# SIM7080G.net
KiCad netlist of a schematic drawn in Altium Designer
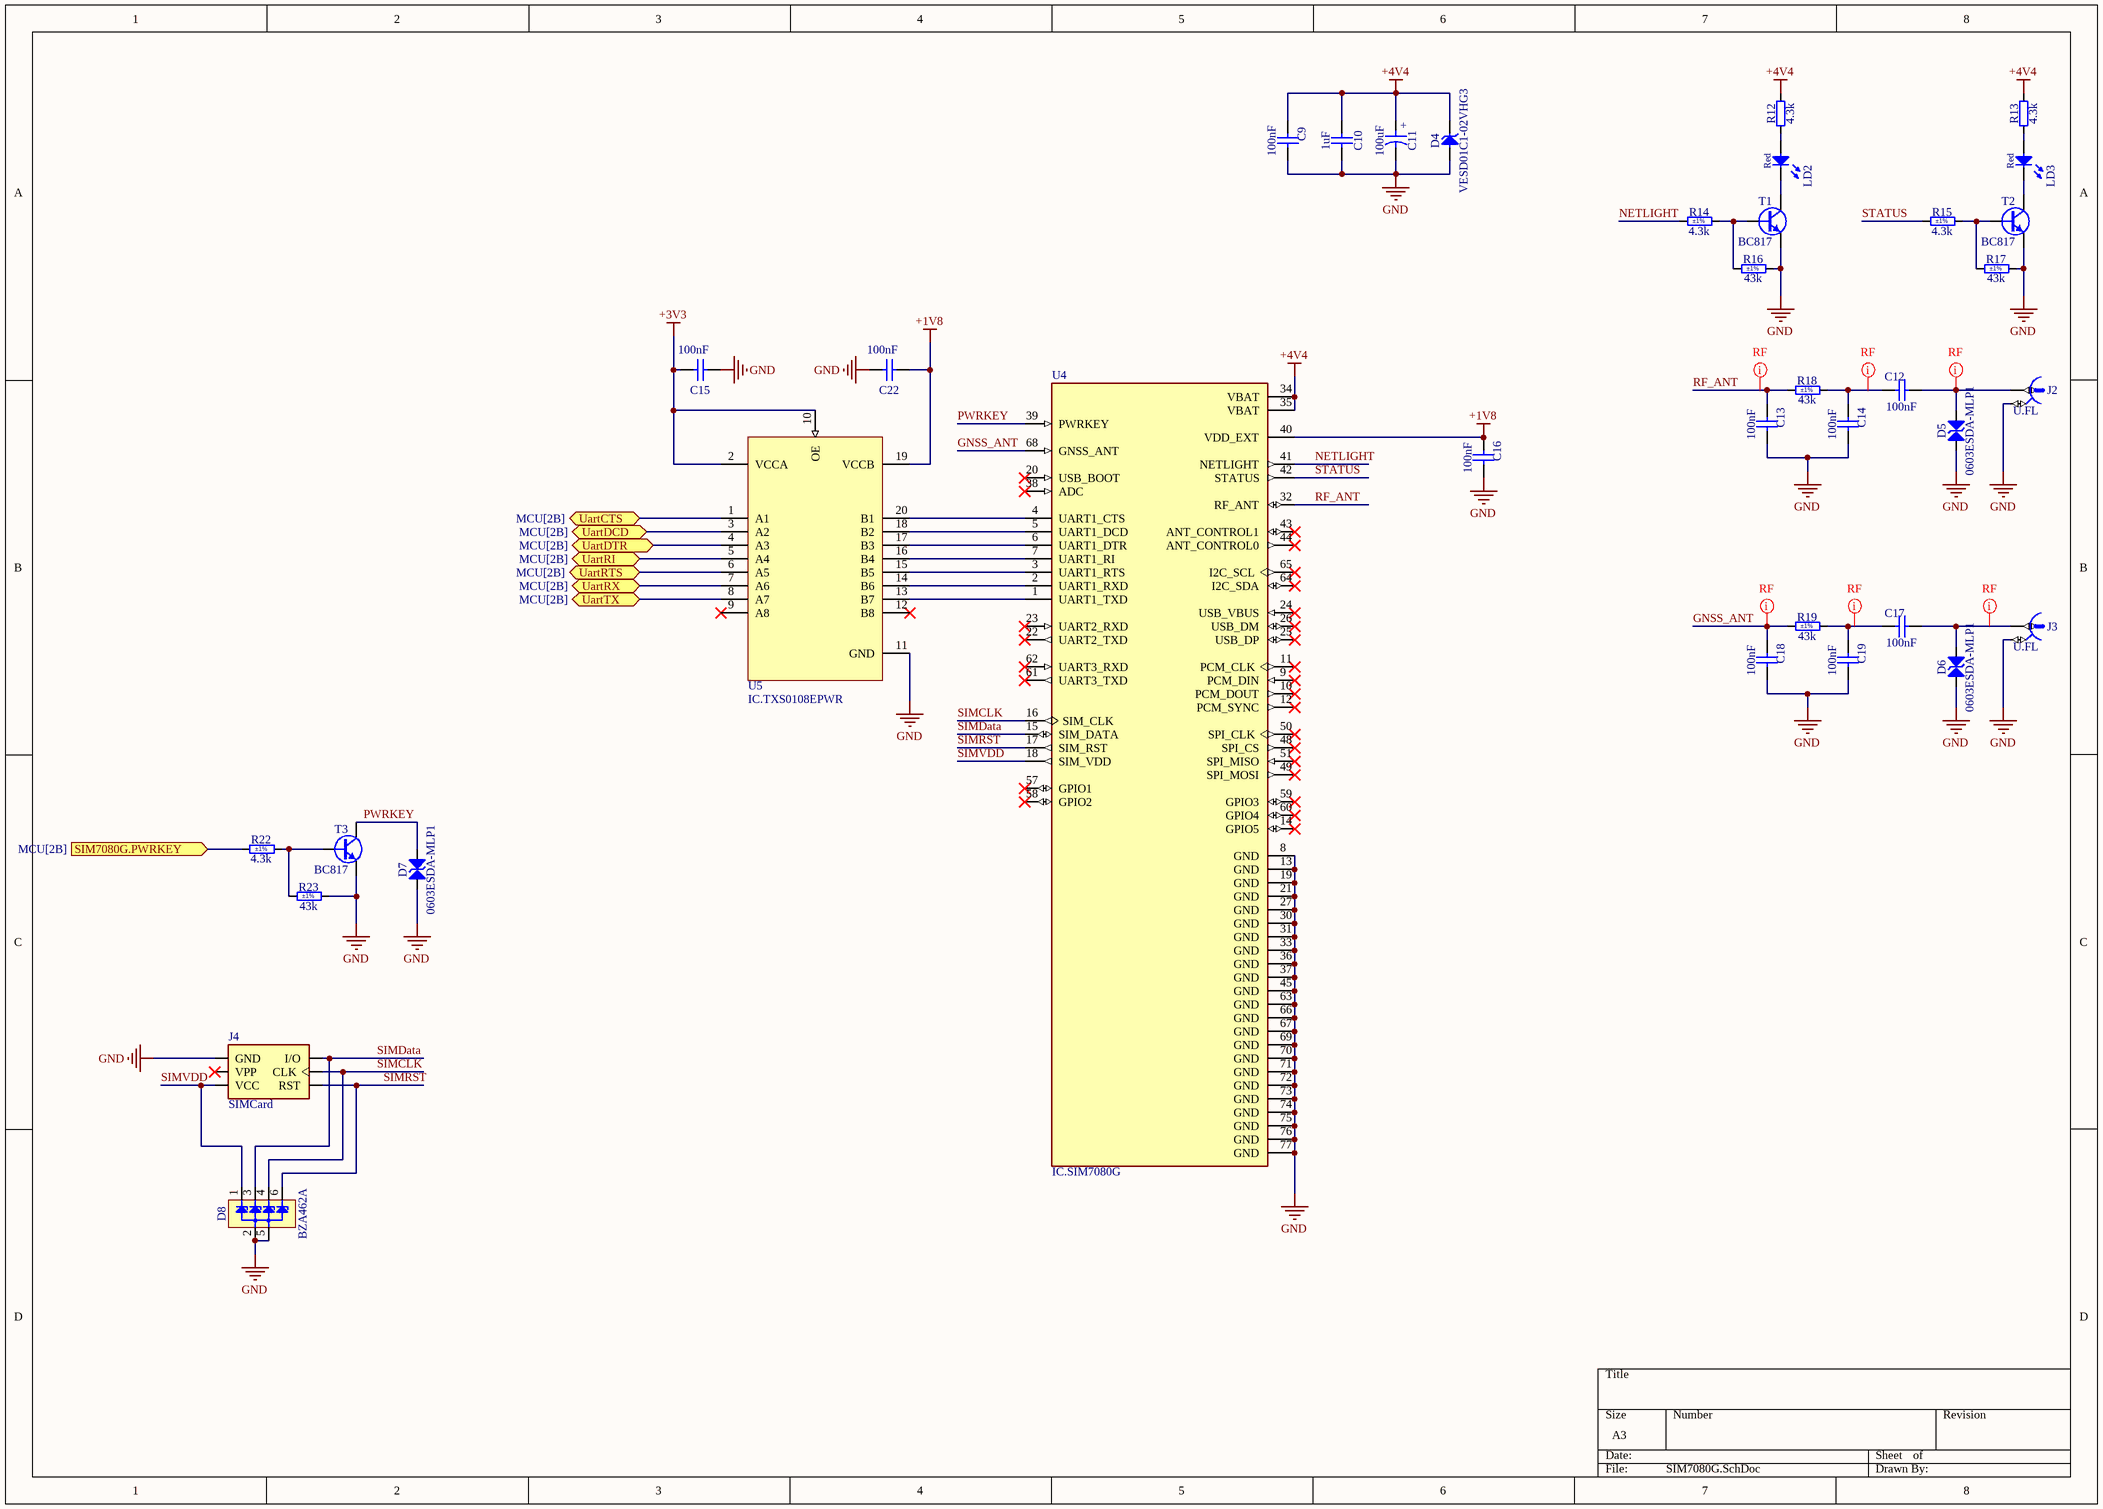
[diagram p0: SIM7080G.SchDoc]

(export (version "E")
  (design (tool "Eeschema 10.0.6"))
  (components
    (comp (ref "C9")
      (value "100nF")
      (footprint "CAPC1608X90N")
      (description "Non-polarised capacitor")
      (fields
        (field (name "PART NUMBER") "CC0603_100NF_25V_20%_X5R_TDK_CGA3E2X5R1E104M080")
        (field (name "VOLTAGE") "25V")
        (field (name "AUTHOR") "CERN DEM BC")
      )
      (libsource (lib "Capacitors") (part "Capacitor - non polarized"))
    )
    (comp (ref "C10")
      (value "1uF")
      (footprint "CAPC1608X90N")
      (description "Non-polarised capacitor")
      (fields
        (field (name "PART NUMBER") "CC0603_1UF_10V_10%_X5R")
        (field (name "VOLTAGE") "10V")
        (field (name "AUTHOR") "CERN DEM HF")
      )
      (libsource (lib "Capacitors") (part "Capacitor - non polarized"))
    )
    (comp (ref "C11")
      (value "100uF")
      (footprint "CAPAE660X540N")
      (description "Polarised capacitor")
      (fields
        (field (name "PART NUMBER") "CAE660-540_100UF_6.3V_20%")
        (field (name "VOLTAGE") "6.3V")
        (field (name "AUTHOR") "CERN DEM JLC")
      )
      (libsource (lib "Capacitors") (part "Capacitor - polarized"))
    )
    (comp (ref "C12")
      (value "100nF")
      (footprint "CAPC1608X90N")
      (description "Non-polarised capacitor")
      (fields
        (field (name "PART NUMBER") "CC0603_100NF_25V_20%_X5R_TDK_CGA3E2X5R1E104M080")
        (field (name "VOLTAGE") "25V")
        (field (name "AUTHOR") "CERN DEM BC")
      )
      (libsource (lib "Capacitors") (part "Capacitor - non polarized"))
    )
    (comp (ref "C13")
      (value "100nF")
      (footprint "CAPC1608X90N")
      (description "Non-polarised capacitor")
      (fields
        (field (name "PART NUMBER") "CC0603_100NF_25V_20%_X5R_TDK_CGA3E2X5R1E104M080")
        (field (name "VOLTAGE") "25V")
        (field (name "AUTHOR") "CERN DEM BC")
      )
      (libsource (lib "Capacitors") (part "Capacitor - non polarized"))
    )
    (comp (ref "C14")
      (value "100nF")
      (footprint "CAPC1608X90N")
      (description "Non-polarised capacitor")
      (fields
        (field (name "PART NUMBER") "CC0603_100NF_25V_20%_X5R_TDK_CGA3E2X5R1E104M080")
        (field (name "VOLTAGE") "25V")
        (field (name "AUTHOR") "CERN DEM BC")
      )
      (libsource (lib "Capacitors") (part "Capacitor - non polarized"))
    )
    (comp (ref "C15")
      (value "100nF")
      (footprint "CAPC1608X90N")
      (description "Non-polarised capacitor")
      (fields
        (field (name "PART NUMBER") "CC0603_100NF_25V_20%_X5R_TDK_CGA3E2X5R1E104M080")
        (field (name "VOLTAGE") "25V")
        (field (name "AUTHOR") "CERN DEM BC")
      )
      (libsource (lib "Capacitors") (part "Capacitor - non polarized"))
    )
    (comp (ref "C16")
      (value "100nF")
      (footprint "CAPC1608X90N")
      (description "Non-polarised capacitor")
      (fields
        (field (name "PART NUMBER") "CC0603_100NF_25V_20%_X5R_TDK_CGA3E2X5R1E104M080")
        (field (name "VOLTAGE") "25V")
        (field (name "AUTHOR") "CERN DEM BC")
      )
      (libsource (lib "Capacitors") (part "Capacitor - non polarized"))
    )
    (comp (ref "C17")
      (value "100nF")
      (footprint "CAPC1608X90N")
      (description "Non-polarised capacitor")
      (fields
        (field (name "PART NUMBER") "CC0603_100NF_25V_20%_X5R_TDK_CGA3E2X5R1E104M080")
        (field (name "VOLTAGE") "25V")
        (field (name "AUTHOR") "CERN DEM BC")
      )
      (libsource (lib "Capacitors") (part "Capacitor - non polarized"))
    )
    (comp (ref "C18")
      (value "100nF")
      (footprint "CAPC1608X90N")
      (description "Non-polarised capacitor")
      (fields
        (field (name "PART NUMBER") "CC0603_100NF_25V_20%_X5R_TDK_CGA3E2X5R1E104M080")
        (field (name "VOLTAGE") "25V")
        (field (name "AUTHOR") "CERN DEM BC")
      )
      (libsource (lib "Capacitors") (part "Capacitor - non polarized"))
    )
    (comp (ref "C19")
      (value "100nF")
      (footprint "CAPC1608X90N")
      (description "Non-polarised capacitor")
      (fields
        (field (name "PART NUMBER") "CC0603_100NF_25V_20%_X5R_TDK_CGA3E2X5R1E104M080")
        (field (name "VOLTAGE") "25V")
        (field (name "AUTHOR") "CERN DEM BC")
      )
      (libsource (lib "Capacitors") (part "Capacitor - non polarized"))
    )
    (comp (ref "C22")
      (value "100nF")
      (footprint "CAPC1608X90N")
      (description "Non-polarised capacitor")
      (fields
        (field (name "PART NUMBER") "CC0603_100NF_25V_20%_X5R_TDK_CGA3E2X5R1E104M080")
        (field (name "VOLTAGE") "25V")
        (field (name "AUTHOR") "CERN DEM BC")
      )
      (libsource (lib "Capacitors") (part "Capacitor - non polarized"))
    )
    (comp (ref "D4")
      (value "VESD01C1-02VHG3")
      (footprint "SODFL1608X70N")
      (description "Transient Voltage Suppressor Diode (Uni-Directional)")
      (fields
        (field (name "VOLTAGE") "1V")
        (field (name "POWER") "100W")
        (field (name "AUTHOR") "CERN DEM BC")
      )
      (libsource (lib "ICs And Semiconductors") (part "Diode TVS Uni-Directional"))
    )
    (comp (ref "D5")
      (value "0603ESDA-MLP1")
      (footprint "EATON_0603ESDA-MLP")
      (description "Transient Voltage Suppressor Diode (Bi-Directional)")
      (fields
        (field (name "VOLTAGE") "8kV")
        (field (name "MANUFACTURER") "EATON")
        (field (name "AUTHOR") "CERN DEM HF")
      )
      (libsource (lib "ICs And Semiconductors") (part "Diode TVS Bi-Directional"))
    )
    (comp (ref "D6")
      (value "0603ESDA-MLP1")
      (footprint "EATON_0603ESDA-MLP")
      (description "Transient Voltage Suppressor Diode (Bi-Directional)")
      (fields
        (field (name "VOLTAGE") "8kV")
        (field (name "MANUFACTURER") "EATON")
        (field (name "AUTHOR") "CERN DEM HF")
      )
      (libsource (lib "ICs And Semiconductors") (part "Diode TVS Bi-Directional"))
    )
    (comp (ref "D7")
      (value "0603ESDA-MLP1")
      (footprint "EATON_0603ESDA-MLP")
      (description "Transient Voltage Suppressor Diode (Bi-Directional)")
      (fields
        (field (name "VOLTAGE") "8kV")
        (field (name "MANUFACTURER") "EATON")
        (field (name "AUTHOR") "CERN DEM HF")
      )
      (libsource (lib "ICs And Semiconductors") (part "Diode TVS Bi-Directional"))
    )
    (comp (ref "D8")
      (value "BZA462A")
      (footprint "SOT95P275X110-6N")
      (description "Quadruple ESD Transient Voltage Suppressor")
      (fields
        (field (name "VOLTAGE") "15kV")
        (field (name "POWER") "24W")
        (field (name "AUTHOR") "CERN DEM JLC")
      )
      (libsource (lib "ICs And Semiconductors") (part "BZA462A"))
    )
    (comp (ref "J2")
      (value "U.FL")
      (footprint "HIROSE_U.FL-R-SMT-1(10)")
      (fields
        (field (name "PART NUMBER") "HIROSE_U.FL-R-SMT-1(10)")
        (field (name "MANUFACTURER") "HIROSE (HRS)")
        (field (name "MANUFACTURER PART NUMBER") "U.FL-R-SMT-1(10)")
        (field (name "AUTHOR") "CERN DEM JLC")
      )
      (libsource (lib "Connectors") (part "Coax_1Male_1Shield"))
    )
    (comp (ref "J3")
      (value "U.FL")
      (footprint "HIROSE_U.FL-R-SMT-1(10)")
      (fields
        (field (name "PART NUMBER") "HIROSE_U.FL-R-SMT-1(10)")
        (field (name "MANUFACTURER") "HIROSE (HRS)")
        (field (name "MANUFACTURER PART NUMBER") "U.FL-R-SMT-1(10)")
        (field (name "AUTHOR") "CERN DEM JLC")
      )
      (libsource (lib "Connectors") (part "Coax_1Male_1Shield"))
    )
    (comp (ref "J4")
      (value "SIMCard")
      (footprint "Connector.SIM805")
      (description "SIM Nano Push Pull 6P1.35mmH with Logo 3µ\" Gold No Peg")
      (fields
        (field (name "MP") "SIM8051-6-0-14-00-X-REVD")
        (field (name "MANUFACTURER") "Global Connector Technology")
      )
      (libsource (lib "ParsaAltiumSCHLIB") (part "Connector.SIM8051"))
    )
    (comp (ref "LD2")
      (value "Red")
      (footprint "LED_DIALIGHT_598-8010-107F")
      (description "LED Red 1C 2A")
      (fields
        (field (name "PART NUMBER") "LED_DIALIGHT_598-8010-107F")
        (field (name "MANUFACTURER") "DIALIGHT")
        (field (name "AUTHOR") "CERN DEM MR")
      )
      (libsource (lib "ICs And Semiconductors") (part "LED Red 1C 2A"))
    )
    (comp (ref "LD3")
      (value "Red")
      (footprint "LED_DIALIGHT_598-8010-107F")
      (description "LED Red 1C 2A")
      (fields
        (field (name "PART NUMBER") "LED_DIALIGHT_598-8010-107F")
        (field (name "MANUFACTURER") "DIALIGHT")
        (field (name "AUTHOR") "CERN DEM MR")
      )
      (libsource (lib "ICs And Semiconductors") (part "LED Red 1C 2A"))
    )
    (comp (ref "R12")
      (value "4.3k")
      (footprint "RESC1608X55N")
      (description "Resistor - 1%")
      (fields
        (field (name "PART NUMBER") "R0603_43K_1%_0.1W_100PPM")
        (field (name "POWER") "0.1W")
        (field (name "AUTHOR") "CERN DEM JLC")
      )
      (libsource (lib "Resistors") (part "Resistor - 1%"))
    )
    (comp (ref "R13")
      (value "4.3k")
      (footprint "RESC1608X55N")
      (description "Resistor - 1%")
      (fields
        (field (name "PART NUMBER") "R0603_43K_1%_0.1W_100PPM")
        (field (name "POWER") "0.1W")
        (field (name "AUTHOR") "CERN DEM JLC")
      )
      (libsource (lib "Resistors") (part "Resistor - 1%"))
    )
    (comp (ref "R14")
      (value "4.3k")
      (footprint "RESC1608X55N")
      (description "Resistor - 1%")
      (fields
        (field (name "TOLERANCE") "±1%")
        (field (name "PART NUMBER") "R0603_43K_1%_0.1W_100PPM")
        (field (name "POWER") "0.1W")
        (field (name "AUTHOR") "CERN DEM JLC")
      )
      (libsource (lib "Resistors") (part "Resistor - 1%"))
    )
    (comp (ref "R15")
      (value "4.3k")
      (footprint "RESC1608X55N")
      (description "Resistor - 1%")
      (fields
        (field (name "TOLERANCE") "±1%")
        (field (name "PART NUMBER") "R0603_43K_1%_0.1W_100PPM")
        (field (name "POWER") "0.1W")
        (field (name "AUTHOR") "CERN DEM JLC")
      )
      (libsource (lib "Resistors") (part "Resistor - 1%"))
    )
    (comp (ref "R16")
      (value "43k")
      (footprint "RESC1608X55N")
      (description "Resistor - 1%")
      (fields
        (field (name "TOLERANCE") "±1%")
        (field (name "PART NUMBER") "R0603_43K_1%_0.1W_100PPM")
        (field (name "POWER") "0.1W")
        (field (name "AUTHOR") "CERN DEM JLC")
      )
      (libsource (lib "Resistors") (part "Resistor - 1%"))
    )
    (comp (ref "R17")
      (value "43k")
      (footprint "RESC1608X55N")
      (description "Resistor - 1%")
      (fields
        (field (name "TOLERANCE") "±1%")
        (field (name "PART NUMBER") "R0603_43K_1%_0.1W_100PPM")
        (field (name "POWER") "0.1W")
        (field (name "AUTHOR") "CERN DEM JLC")
      )
      (libsource (lib "Resistors") (part "Resistor - 1%"))
    )
    (comp (ref "R18")
      (value "43k")
      (footprint "RESC1608X55N")
      (description "Resistor - 1%")
      (fields
        (field (name "TOLERANCE") "±1%")
        (field (name "PART NUMBER") "R0603_43K_1%_0.1W_100PPM")
        (field (name "POWER") "0.1W")
        (field (name "AUTHOR") "CERN DEM JLC")
      )
      (libsource (lib "Resistors") (part "Resistor - 1%"))
    )
    (comp (ref "R19")
      (value "43k")
      (footprint "RESC1608X55N")
      (description "Resistor - 1%")
      (fields
        (field (name "TOLERANCE") "±1%")
        (field (name "PART NUMBER") "R0603_43K_1%_0.1W_100PPM")
        (field (name "POWER") "0.1W")
        (field (name "AUTHOR") "CERN DEM JLC")
      )
      (libsource (lib "Resistors") (part "Resistor - 1%"))
    )
    (comp (ref "R22")
      (value "4.3k")
      (footprint "RESC1608X55N")
      (description "Resistor - 1%")
      (fields
        (field (name "TOLERANCE") "±1%")
        (field (name "PART NUMBER") "R0603_43K_1%_0.1W_100PPM")
        (field (name "POWER") "0.1W")
        (field (name "AUTHOR") "CERN DEM JLC")
      )
      (libsource (lib "Resistors") (part "Resistor - 1%"))
    )
    (comp (ref "R23")
      (value "43k")
      (footprint "RESC1608X55N")
      (description "Resistor - 1%")
      (fields
        (field (name "TOLERANCE") "±1%")
        (field (name "PART NUMBER") "R0603_43K_1%_0.1W_100PPM")
        (field (name "POWER") "0.1W")
        (field (name "AUTHOR") "CERN DEM JLC")
      )
      (libsource (lib "Resistors") (part "Resistor - 1%"))
    )
    (comp (ref "T1")
      (value "BC817")
      (footprint "SOT95P230X110-3N")
      (description "NPN Transistor")
      (fields (field (name "MANUFACTURER") "NXP SEMICONDUCTORS") (field (name "AUTHOR") "CERN DEM JLC"))
      (libsource (lib "ICs And Semiconductors") (part "NPN B1 E2 C3"))
    )
    (comp (ref "T2")
      (value "BC817")
      (footprint "SOT95P230X110-3N")
      (description "NPN Transistor")
      (fields (field (name "MANUFACTURER") "NXP SEMICONDUCTORS") (field (name "AUTHOR") "CERN DEM JLC"))
      (libsource (lib "ICs And Semiconductors") (part "NPN B1 E2 C3"))
    )
    (comp (ref "T3")
      (value "BC817")
      (footprint "SOT95P230X110-3N")
      (description "NPN Transistor")
      (fields (field (name "MANUFACTURER") "NXP SEMICONDUCTORS") (field (name "AUTHOR") "CERN DEM JLC"))
      (libsource (lib "ICs And Semiconductors") (part "NPN B1 E2 C3"))
    )
    (comp (ref "U4")
      (value "IC.SIM7080G")
      (footprint "IC.SIM7080G")
      (fields (field (name "MF") "SIMCom") (field (name "MP") "SIM7080G"))
      (libsource (lib "ParsaAltiumSCHLIB") (part "IC.SIM7080G"))
    )
    (comp (ref "U5")
      (value "IC.TXS0108EPWR")
      (footprint "IC.TXS0108EPWR")
      (description "8-bit bidirectional voltage-level shifter for open-drain and push-pull application")
      (fields (field (name "MF") "Texas Instruments") (field (name "MP") "TXS0108EPWR"))
      (libsource (lib "ParsaAltiumSCHLIB") (part "IC.TXS0108EPWR"))
    )
  )
  (nets
    (net (code "1") (name "+1V8") (class "Default")
      (node (ref "C16") (pin "1") (pinfunction "1_1") (pintype "passive"))
      (node (ref "C22") (pin "2") (pinfunction "2_2") (pintype "passive"))
      (node (ref "U4") (pin "40") (pinfunction "VDD_EXT_40") (pintype "passive"))
      (node (ref "U5") (pin "19") (pinfunction "VCCB_19") (pintype "power_in"))
    )
    (net (code "2") (name "+3V3") (class "Default")
      (node (ref "C15") (pin "1") (pinfunction "1_1") (pintype "passive"))
      (node (ref "U5") (pin "10") (pinfunction "OE_10") (pintype "input"))
      (node (ref "U5") (pin "2") (pinfunction "VCCA_2") (pintype "power_in"))
    )
    (net (code "3") (name "+4V4") (class "Default")
      (node (ref "C10") (pin "1") (pinfunction "1_1") (pintype "passive"))
      (node (ref "C11") (pin "1") (pinfunction "1_1") (pintype "passive"))
      (node (ref "C9") (pin "1") (pinfunction "1_1") (pintype "passive"))
      (node (ref "D4") (pin "1") (pinfunction "C_1") (pintype "passive"))
      (node (ref "R12") (pin "2") (pinfunction "2_2") (pintype "passive"))
      (node (ref "R13") (pin "2") (pinfunction "2_2") (pintype "passive"))
      (node (ref "U4") (pin "34") (pinfunction "VBAT_34") (pintype "power_in"))
      (node (ref "U4") (pin "35") (pinfunction "VBAT_35") (pintype "power_in"))
    )
    (net (code "4") (name "/GNSS_ANT") (class "Default")
      (node (ref "C18") (pin "1") (pinfunction "1_1") (pintype "passive"))
      (node (ref "R19") (pin "1") (pinfunction "1_1") (pintype "passive"))
      (node (ref "U4") (pin "68") (pinfunction "GNSS_ANT_68") (pintype "input"))
    )
    (net (code "5") (name "/NETLIGHT") (class "Default")
      (node (ref "R14") (pin "1") (pinfunction "1_1") (pintype "passive"))
      (node (ref "U4") (pin "41") (pinfunction "NETLIGHT_41") (pintype "output"))
    )
    (net (code "6") (name "/PWRKEY") (class "Default")
      (node (ref "D7") (pin "2") (pinfunction "2_2") (pintype "passive"))
      (node (ref "T3") (pin "3") (pinfunction "C_3") (pintype "passive"))
      (node (ref "U4") (pin "39") (pinfunction "PWRKEY_39") (pintype "input"))
    )
    (net (code "7") (name "/RF_ANT") (class "Default")
      (node (ref "C13") (pin "1") (pinfunction "1_1") (pintype "passive"))
      (node (ref "R18") (pin "1") (pinfunction "1_1") (pintype "passive"))
      (node (ref "U4") (pin "32") (pinfunction "RF_ANT_32") (pintype "bidirectional"))
    )
    (net (code "8") (name "/SIM7080G.PWRKEY") (class "Default")
      (node (ref "R22") (pin "1") (pinfunction "1_1") (pintype "passive"))
    )
    (net (code "9") (name "/SIMCLK") (class "Default")
      (node (ref "D8") (pin "4") (pinfunction "C3_4") (pintype "passive"))
      (node (ref "J4") (pin "C3") (pinfunction "CLK_C3") (pintype "passive"))
      (node (ref "U4") (pin "16") (pinfunction "SIM_CLK_16") (pintype "output"))
    )
    (net (code "10") (name "/SIMData") (class "Default")
      (node (ref "D8") (pin "3") (pinfunction "C2_3") (pintype "passive"))
      (node (ref "J4") (pin "C7") (pinfunction "I/O_C7") (pintype "passive"))
      (node (ref "U4") (pin "15") (pinfunction "SIM_DATA_15") (pintype "bidirectional"))
    )
    (net (code "11") (name "/SIMRST") (class "Default")
      (node (ref "D8") (pin "6") (pinfunction "C4_6") (pintype "passive"))
      (node (ref "J4") (pin "C2") (pinfunction "RST_C2") (pintype "passive"))
      (node (ref "U4") (pin "17") (pinfunction "SIM_RST_17") (pintype "output"))
    )
    (net (code "12") (name "/SIMVDD") (class "Default")
      (node (ref "D8") (pin "1") (pinfunction "C1_1") (pintype "passive"))
      (node (ref "J4") (pin "C1") (pinfunction "VCC_C1") (pintype "passive"))
      (node (ref "U4") (pin "18") (pinfunction "SIM_VDD_18") (pintype "output"))
    )
    (net (code "13") (name "/STATUS") (class "Default")
      (node (ref "R15") (pin "1") (pinfunction "1_1") (pintype "passive"))
      (node (ref "U4") (pin "42") (pinfunction "STATUS_42") (pintype "output"))
    )
    (net (code "14") (name "/UartCTS") (class "Default")
      (node (ref "U5") (pin "1") (pinfunction "A1_1") (pintype "passive"))
    )
    (net (code "15") (name "/UartDCD") (class "Default")
      (node (ref "U5") (pin "3") (pinfunction "A2_3") (pintype "passive"))
    )
    (net (code "16") (name "/UartDTR") (class "Default")
      (node (ref "U5") (pin "4") (pinfunction "A3_4") (pintype "passive"))
    )
    (net (code "17") (name "/UartRI") (class "Default")
      (node (ref "U5") (pin "5") (pinfunction "A4_5") (pintype "passive"))
    )
    (net (code "18") (name "/UartRTS") (class "Default")
      (node (ref "U5") (pin "6") (pinfunction "A5_6") (pintype "passive"))
    )
    (net (code "19") (name "/UartRX") (class "Default")
      (node (ref "U5") (pin "7") (pinfunction "A6_7") (pintype "passive"))
    )
    (net (code "20") (name "/UartTX") (class "Default")
      (node (ref "U5") (pin "8") (pinfunction "A7_8") (pintype "passive"))
    )
    (net (code "21") (name "GND") (class "Default")
      (node (ref "C10") (pin "2") (pinfunction "2_2") (pintype "passive"))
      (node (ref "C11") (pin "2") (pinfunction "2_2") (pintype "passive"))
      (node (ref "C13") (pin "2") (pinfunction "2_2") (pintype "passive"))
      (node (ref "C14") (pin "2") (pinfunction "2_2") (pintype "passive"))
      (node (ref "C15") (pin "2") (pinfunction "2_2") (pintype "passive"))
      (node (ref "C16") (pin "2") (pinfunction "2_2") (pintype "passive"))
      (node (ref "C18") (pin "2") (pinfunction "2_2") (pintype "passive"))
      (node (ref "C19") (pin "2") (pinfunction "2_2") (pintype "passive"))
      (node (ref "C22") (pin "1") (pinfunction "1_1") (pintype "passive"))
      (node (ref "C9") (pin "2") (pinfunction "2_2") (pintype "passive"))
      (node (ref "D4") (pin "2") (pinfunction "A_2") (pintype "passive"))
      (node (ref "D5") (pin "1") (pinfunction "1_1") (pintype "passive"))
      (node (ref "D6") (pin "1") (pinfunction "1_1") (pintype "passive"))
      (node (ref "D7") (pin "1") (pinfunction "1_1") (pintype "passive"))
      (node (ref "D8") (pin "2") (pinfunction "A_2") (pintype "passive"))
      (node (ref "D8") (pin "5") (pinfunction "A_5") (pintype "passive"))
      (node (ref "J2") (pin "2") (pinfunction "2_2") (pintype "bidirectional"))
      (node (ref "J3") (pin "2") (pinfunction "2_2") (pintype "bidirectional"))
      (node (ref "J4") (pin "C5") (pinfunction "GND_C5") (pintype "passive"))
      (node (ref "R16") (pin "2") (pinfunction "2_2") (pintype "passive"))
      (node (ref "R17") (pin "2") (pinfunction "2_2") (pintype "passive"))
      (node (ref "R23") (pin "2") (pinfunction "2_2") (pintype "passive"))
      (node (ref "T1") (pin "2") (pinfunction "E_2") (pintype "passive"))
      (node (ref "T2") (pin "2") (pinfunction "E_2") (pintype "passive"))
      (node (ref "T3") (pin "2") (pinfunction "E_2") (pintype "passive"))
      (node (ref "U4") (pin "13") (pinfunction "GND_13") (pintype "power_in"))
      (node (ref "U4") (pin "19") (pinfunction "GND_19") (pintype "power_in"))
      (node (ref "U4") (pin "21") (pinfunction "GND_21") (pintype "power_in"))
      (node (ref "U4") (pin "27") (pinfunction "GND_27") (pintype "power_in"))
      (node (ref "U4") (pin "30") (pinfunction "GND_30") (pintype "power_in"))
      (node (ref "U4") (pin "31") (pinfunction "GND_31") (pintype "power_in"))
      (node (ref "U4") (pin "33") (pinfunction "GND_33") (pintype "power_in"))
      (node (ref "U4") (pin "36") (pinfunction "GND_36") (pintype "power_in"))
      (node (ref "U4") (pin "37") (pinfunction "GND_37") (pintype "power_in"))
      (node (ref "U4") (pin "45") (pinfunction "GND_45") (pintype "power_in"))
      (node (ref "U4") (pin "63") (pinfunction "GND_63") (pintype "power_in"))
      (node (ref "U4") (pin "66") (pinfunction "GND_66") (pintype "power_in"))
      (node (ref "U4") (pin "67") (pinfunction "GND_67") (pintype "power_in"))
      (node (ref "U4") (pin "69") (pinfunction "GND_69") (pintype "power_in"))
      (node (ref "U4") (pin "70") (pinfunction "GND_70") (pintype "power_in"))
      (node (ref "U4") (pin "71") (pinfunction "GND_71") (pintype "power_in"))
      (node (ref "U4") (pin "72") (pinfunction "GND_72") (pintype "power_in"))
      (node (ref "U4") (pin "73") (pinfunction "GND_73") (pintype "power_in"))
      (node (ref "U4") (pin "74") (pinfunction "GND_74") (pintype "power_in"))
      (node (ref "U4") (pin "75") (pinfunction "GND_75") (pintype "power_in"))
      (node (ref "U4") (pin "76") (pinfunction "GND_76") (pintype "power_in"))
      (node (ref "U4") (pin "77") (pinfunction "GND_77") (pintype "power_in"))
      (node (ref "U4") (pin "8") (pinfunction "GND_8") (pintype "power_in"))
      (node (ref "U5") (pin "11") (pinfunction "GND_11") (pintype "power_in"))
    )
    (net (code "22") (name "Net-(C12-Pad1)") (class "Default")
      (node (ref "C12") (pin "1") (pinfunction "1_1") (pintype "passive"))
      (node (ref "C14") (pin "1") (pinfunction "1_1") (pintype "passive"))
      (node (ref "R18") (pin "2") (pinfunction "2_2") (pintype "passive"))
    )
    (net (code "23") (name "Net-(C12-Pad2)") (class "Default")
      (node (ref "C12") (pin "2") (pinfunction "2_2") (pintype "passive"))
      (node (ref "D5") (pin "2") (pinfunction "2_2") (pintype "passive"))
      (node (ref "J2") (pin "1") (pinfunction "1_1") (pintype "bidirectional"))
    )
    (net (code "24") (name "Net-(C17-Pad1)") (class "Default")
      (node (ref "C17") (pin "1") (pinfunction "1_1") (pintype "passive"))
      (node (ref "C19") (pin "1") (pinfunction "1_1") (pintype "passive"))
      (node (ref "R19") (pin "2") (pinfunction "2_2") (pintype "passive"))
    )
    (net (code "25") (name "Net-(C17-Pad2)") (class "Default")
      (node (ref "C17") (pin "2") (pinfunction "2_2") (pintype "passive"))
      (node (ref "D6") (pin "2") (pinfunction "2_2") (pintype "passive"))
      (node (ref "J3") (pin "1") (pinfunction "1_1") (pintype "bidirectional"))
    )
    (net (code "26") (name "Net-(LD2-A)") (class "Default")
      (node (ref "LD2") (pin "2") (pinfunction "A_2") (pintype "passive"))
      (node (ref "R12") (pin "1") (pinfunction "1_1") (pintype "passive"))
    )
    (net (code "27") (name "Net-(LD2-C)") (class "Default")
      (node (ref "LD2") (pin "1") (pinfunction "C_1") (pintype "passive"))
      (node (ref "T1") (pin "3") (pinfunction "C_3") (pintype "passive"))
    )
    (net (code "28") (name "Net-(LD3-A)") (class "Default")
      (node (ref "LD3") (pin "2") (pinfunction "A_2") (pintype "passive"))
      (node (ref "R13") (pin "1") (pinfunction "1_1") (pintype "passive"))
    )
    (net (code "29") (name "Net-(LD3-C)") (class "Default")
      (node (ref "LD3") (pin "1") (pinfunction "C_1") (pintype "passive"))
      (node (ref "T2") (pin "3") (pinfunction "C_3") (pintype "passive"))
    )
    (net (code "30") (name "Net-(T1-B)") (class "Default")
      (node (ref "R14") (pin "2") (pinfunction "2_2") (pintype "passive"))
      (node (ref "R16") (pin "1") (pinfunction "1_1") (pintype "passive"))
      (node (ref "T1") (pin "1") (pinfunction "B_1") (pintype "passive"))
    )
    (net (code "31") (name "Net-(T2-B)") (class "Default")
      (node (ref "R15") (pin "2") (pinfunction "2_2") (pintype "passive"))
      (node (ref "R17") (pin "1") (pinfunction "1_1") (pintype "passive"))
      (node (ref "T2") (pin "1") (pinfunction "B_1") (pintype "passive"))
    )
    (net (code "32") (name "Net-(T3-B)") (class "Default")
      (node (ref "R22") (pin "2") (pinfunction "2_2") (pintype "passive"))
      (node (ref "R23") (pin "1") (pinfunction "1_1") (pintype "passive"))
      (node (ref "T3") (pin "1") (pinfunction "B_1") (pintype "passive"))
    )
    (net (code "33") (name "Net-(U4-UART1_CTS)") (class "Default")
      (node (ref "U4") (pin "4") (pinfunction "UART1_CTS_4") (pintype "passive"))
      (node (ref "U5") (pin "20") (pinfunction "B1_20") (pintype "passive"))
    )
    (net (code "34") (name "Net-(U4-UART1_DCD)") (class "Default")
      (node (ref "U4") (pin "5") (pinfunction "UART1_DCD_5") (pintype "passive"))
      (node (ref "U5") (pin "18") (pinfunction "B2_18") (pintype "passive"))
    )
    (net (code "35") (name "Net-(U4-UART1_DTR)") (class "Default")
      (node (ref "U4") (pin "6") (pinfunction "UART1_DTR_6") (pintype "passive"))
      (node (ref "U5") (pin "17") (pinfunction "B3_17") (pintype "passive"))
    )
    (net (code "36") (name "Net-(U4-UART1_RI)") (class "Default")
      (node (ref "U4") (pin "7") (pinfunction "UART1_RI_7") (pintype "passive"))
      (node (ref "U5") (pin "16") (pinfunction "B4_16") (pintype "passive"))
    )
    (net (code "37") (name "Net-(U4-UART1_RTS)") (class "Default")
      (node (ref "U4") (pin "3") (pinfunction "UART1_RTS_3") (pintype "passive"))
      (node (ref "U5") (pin "15") (pinfunction "B5_15") (pintype "passive"))
    )
    (net (code "38") (name "Net-(U4-UART1_RXD)") (class "Default")
      (node (ref "U4") (pin "2") (pinfunction "UART1_RXD_2") (pintype "passive"))
      (node (ref "U5") (pin "14") (pinfunction "B6_14") (pintype "passive"))
    )
    (net (code "39") (name "Net-(U4-UART1_TXD)") (class "Default")
      (node (ref "U4") (pin "1") (pinfunction "UART1_TXD_1") (pintype "passive"))
      (node (ref "U5") (pin "13") (pinfunction "B7_13") (pintype "passive"))
    )
    (net (code "40") (name "unconnected-(J4-VPP-PadC6)") (class "Default")
      (node (ref "J4") (pin "C6") (pinfunction "VPP_C6") (pintype "passive+no_connect"))
    )
    (net (code "41") (name "unconnected-(U4-ADC-Pad38)") (class "Default")
      (node (ref "U4") (pin "38") (pinfunction "ADC_38") (pintype "input+no_connect"))
    )
    (net (code "42") (name "unconnected-(U4-ANT_CONTROL0-Pad44)") (class "Default")
      (node (ref "U4") (pin "44") (pinfunction "ANT_CONTROL0_44") (pintype "output+no_connect"))
    )
    (net (code "43") (name "unconnected-(U4-ANT_CONTROL1-Pad43)") (class "Default")
      (node (ref "U4") (pin "43") (pinfunction "ANT_CONTROL1_43") (pintype "bidirectional+no_connect"))
    )
    (net (code "44") (name "unconnected-(U4-GPIO1-Pad57)") (class "Default")
      (node (ref "U4") (pin "57") (pinfunction "GPIO1_57") (pintype "bidirectional+no_connect"))
    )
    (net (code "45") (name "unconnected-(U4-GPIO2-Pad58)") (class "Default")
      (node (ref "U4") (pin "58") (pinfunction "GPIO2_58") (pintype "bidirectional+no_connect"))
    )
    (net (code "46") (name "unconnected-(U4-GPIO3-Pad59)") (class "Default")
      (node (ref "U4") (pin "59") (pinfunction "GPIO3_59") (pintype "bidirectional+no_connect"))
    )
    (net (code "47") (name "unconnected-(U4-GPIO4-Pad60)") (class "Default")
      (node (ref "U4") (pin "60") (pinfunction "GPIO4_60") (pintype "bidirectional+no_connect"))
    )
    (net (code "48") (name "unconnected-(U4-GPIO5-Pad14)") (class "Default")
      (node (ref "U4") (pin "14") (pinfunction "GPIO5_14") (pintype "bidirectional+no_connect"))
    )
    (net (code "49") (name "unconnected-(U4-I2C_SCL-Pad65)") (class "Default")
      (node (ref "U4") (pin "65") (pinfunction "I2C_SCL_65") (pintype "output+no_connect"))
    )
    (net (code "50") (name "unconnected-(U4-I2C_SDA-Pad64)") (class "Default")
      (node (ref "U4") (pin "64") (pinfunction "I2C_SDA_64") (pintype "bidirectional+no_connect"))
    )
    (net (code "51") (name "unconnected-(U4-PCM_CLK-Pad11)") (class "Default")
      (node (ref "U4") (pin "11") (pinfunction "PCM_CLK_11") (pintype "output+no_connect"))
    )
    (net (code "52") (name "unconnected-(U4-PCM_DIN-Pad9)") (class "Default")
      (node (ref "U4") (pin "9") (pinfunction "PCM_DIN_9") (pintype "input+no_connect"))
    )
    (net (code "53") (name "unconnected-(U4-PCM_DOUT-Pad10)") (class "Default")
      (node (ref "U4") (pin "10") (pinfunction "PCM_DOUT_10") (pintype "output+no_connect"))
    )
    (net (code "54") (name "unconnected-(U4-PCM_SYNC-Pad12)") (class "Default")
      (node (ref "U4") (pin "12") (pinfunction "PCM_SYNC_12") (pintype "output+no_connect"))
    )
    (net (code "55") (name "unconnected-(U4-SPI_CLK-Pad50)") (class "Default")
      (node (ref "U4") (pin "50") (pinfunction "SPI_CLK_50") (pintype "output+no_connect"))
    )
    (net (code "56") (name "unconnected-(U4-SPI_CS-Pad48)") (class "Default")
      (node (ref "U4") (pin "48") (pinfunction "SPI_CS_48") (pintype "output+no_connect"))
    )
    (net (code "57") (name "unconnected-(U4-SPI_MISO-Pad51)") (class "Default")
      (node (ref "U4") (pin "51") (pinfunction "SPI_MISO_51") (pintype "input+no_connect"))
    )
    (net (code "58") (name "unconnected-(U4-SPI_MOSI-Pad49)") (class "Default")
      (node (ref "U4") (pin "49") (pinfunction "SPI_MOSI_49") (pintype "output+no_connect"))
    )
    (net (code "59") (name "unconnected-(U4-UART2_RXD-Pad23)") (class "Default")
      (node (ref "U4") (pin "23") (pinfunction "UART2_RXD_23") (pintype "input+no_connect"))
    )
    (net (code "60") (name "unconnected-(U4-UART2_TXD-Pad22)") (class "Default")
      (node (ref "U4") (pin "22") (pinfunction "UART2_TXD_22") (pintype "output+no_connect"))
    )
    (net (code "61") (name "unconnected-(U4-UART3_RXD-Pad62)") (class "Default")
      (node (ref "U4") (pin "62") (pinfunction "UART3_RXD_62") (pintype "input+no_connect"))
    )
    (net (code "62") (name "unconnected-(U4-UART3_TXD-Pad61)") (class "Default")
      (node (ref "U4") (pin "61") (pinfunction "UART3_TXD_61") (pintype "output+no_connect"))
    )
    (net (code "63") (name "unconnected-(U4-USB_BOOT-Pad20)") (class "Default")
      (node (ref "U4") (pin "20") (pinfunction "USB_BOOT_20") (pintype "input+no_connect"))
    )
    (net (code "64") (name "unconnected-(U4-USB_DM-Pad26)") (class "Default")
      (node (ref "U4") (pin "26") (pinfunction "USB_DM_26") (pintype "bidirectional+no_connect"))
    )
    (net (code "65") (name "unconnected-(U4-USB_DP-Pad25)") (class "Default")
      (node (ref "U4") (pin "25") (pinfunction "USB_DP_25") (pintype "bidirectional+no_connect"))
    )
    (net (code "66") (name "unconnected-(U4-USB_VBUS-Pad24)") (class "Default")
      (node (ref "U4") (pin "24") (pinfunction "USB_VBUS_24") (pintype "input+no_connect"))
    )
    (net (code "67") (name "unconnected-(U5-A8-Pad9)") (class "Default")
      (node (ref "U5") (pin "9") (pinfunction "A8_9") (pintype "passive+no_connect"))
    )
    (net (code "68") (name "unconnected-(U5-B8-Pad12)") (class "Default")
      (node (ref "U5") (pin "12") (pinfunction "B8_12") (pintype "passive+no_connect"))
    )
  )
)
